# 8T49N241-999NLGI.net
KiCad netlist of a schematic drawn in Altium Designer
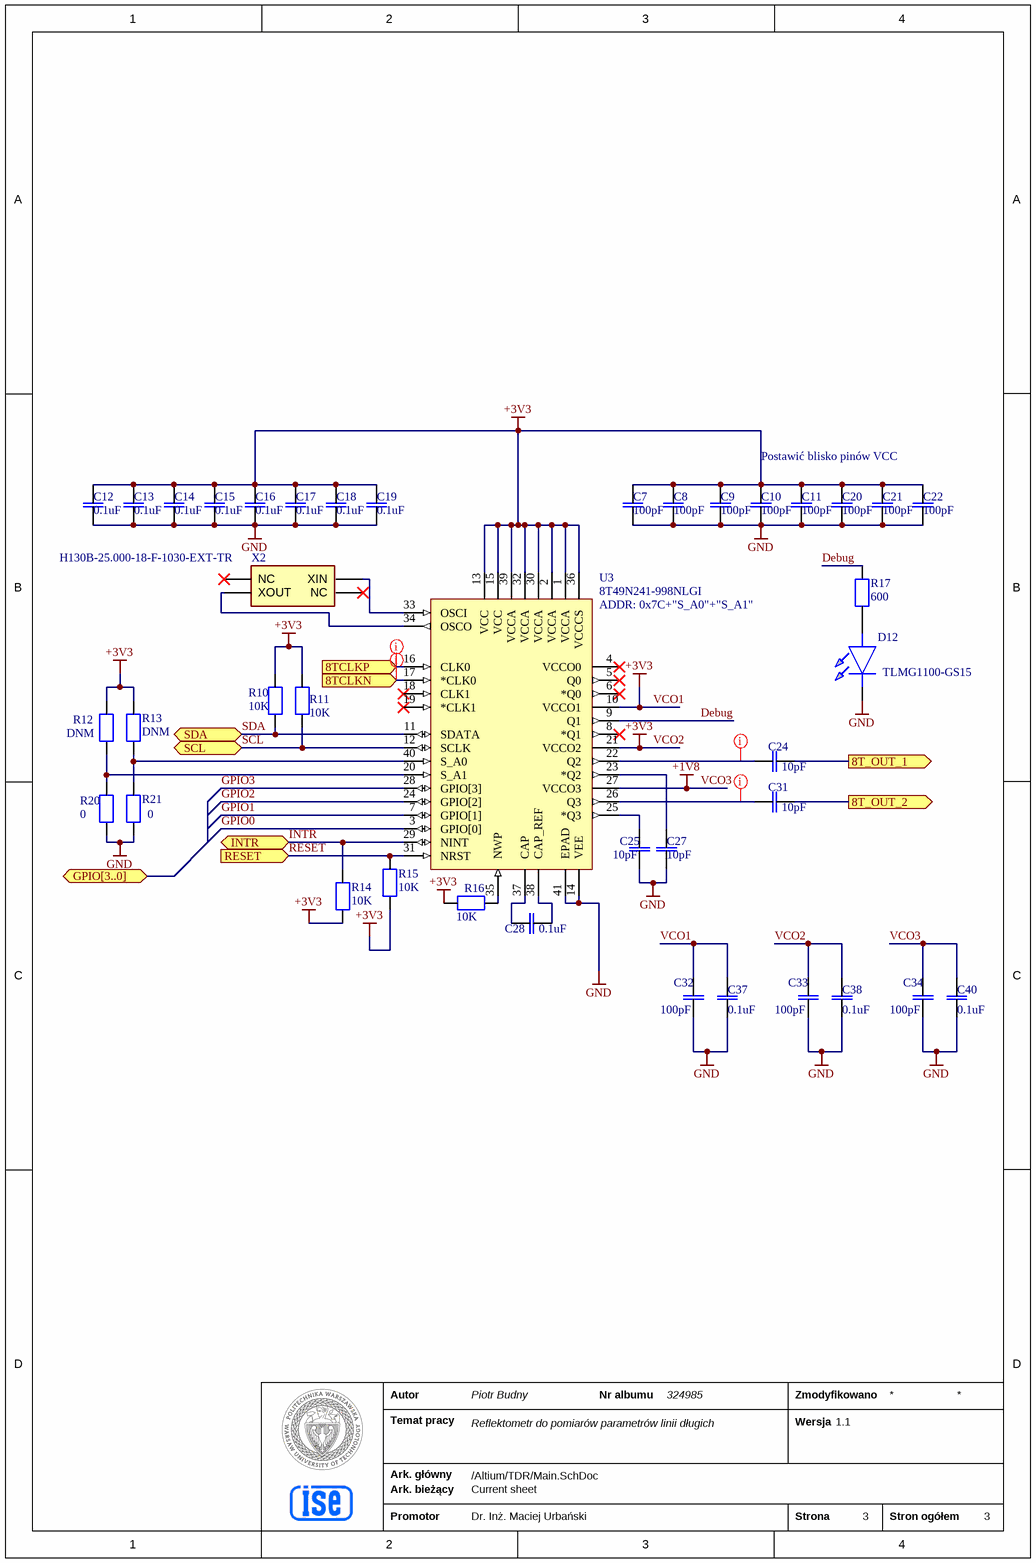
[diagram p0: 8T49N241-999NLGI.SchDoc]

(export (version "E")
  (design (tool "Eeschema 10.0.6"))
  (components
    (comp (ref "C7")
      (value "100pF")
      (footprint "CAPC0603")
      (description "No Description Available")
      (fields
        (field (name "MANUFACTURER_PART_NUMBER") "C0805X399C8HAC7800")
        (field (name "COPYRIGHT") "Copyright (C) 2025 Ultra Librarian. All rights reserved.")
      )
      (libsource (lib "TDR_int_lib") (part "C0603"))
    )
    (comp (ref "C8")
      (value "100pF")
      (footprint "CAPC0603")
      (description "No Description Available")
      (fields
        (field (name "MANUFACTURER_PART_NUMBER") "C0805X399C8HAC7800")
        (field (name "COPYRIGHT") "Copyright (C) 2025 Ultra Librarian. All rights reserved.")
      )
      (libsource (lib "TDR_int_lib") (part "C0603"))
    )
    (comp (ref "C9")
      (value "100pF")
      (footprint "CAPC0603")
      (description "No Description Available")
      (fields
        (field (name "MANUFACTURER_PART_NUMBER") "C0805X399C8HAC7800")
        (field (name "COPYRIGHT") "Copyright (C) 2025 Ultra Librarian. All rights reserved.")
      )
      (libsource (lib "TDR_int_lib") (part "C0603"))
    )
    (comp (ref "C10")
      (value "100pF")
      (footprint "CAPC0603")
      (description "No Description Available")
      (fields
        (field (name "MANUFACTURER_PART_NUMBER") "C0805X399C8HAC7800")
        (field (name "COPYRIGHT") "Copyright (C) 2025 Ultra Librarian. All rights reserved.")
      )
      (libsource (lib "TDR_int_lib") (part "C0603"))
    )
    (comp (ref "C11")
      (value "100pF")
      (footprint "CAPC0603")
      (description "No Description Available")
      (fields
        (field (name "MANUFACTURER_PART_NUMBER") "C0805X399C8HAC7800")
        (field (name "COPYRIGHT") "Copyright (C) 2025 Ultra Librarian. All rights reserved.")
      )
      (libsource (lib "TDR_int_lib") (part "C0603"))
    )
    (comp (ref "C12")
      (value "0.1uF")
      (footprint "CAPC0603")
      (description "CAP SMD 0805")
      (fields
        (field (name "MANUFACTURER_PART_NUMBER") "C0805X399C8HAC7800")
        (field (name "COPYRIGHT") "Copyright (C) 2025 Ultra Librarian. All rights reserved.")
      )
      (libsource (lib "TDR_int_lib") (part "C0603"))
    )
    (comp (ref "C13")
      (value "0.1uF")
      (footprint "CAPC0603")
      (description "CAP SMD 0805")
      (fields
        (field (name "MANUFACTURER_PART_NUMBER") "C0805X399C8HAC7800")
        (field (name "COPYRIGHT") "Copyright (C) 2025 Ultra Librarian. All rights reserved.")
      )
      (libsource (lib "TDR_int_lib") (part "C0603"))
    )
    (comp (ref "C14")
      (value "0.1uF")
      (footprint "CAPC0603")
      (description "CAP SMD 0805")
      (fields
        (field (name "MANUFACTURER_PART_NUMBER") "C0805X399C8HAC7800")
        (field (name "COPYRIGHT") "Copyright (C) 2025 Ultra Librarian. All rights reserved.")
      )
      (libsource (lib "TDR_int_lib") (part "C0603"))
    )
    (comp (ref "C15")
      (value "0.1uF")
      (footprint "CAPC0603")
      (description "CAP SMD 0805")
      (fields
        (field (name "MANUFACTURER_PART_NUMBER") "C0805X399C8HAC7800")
        (field (name "COPYRIGHT") "Copyright (C) 2025 Ultra Librarian. All rights reserved.")
      )
      (libsource (lib "TDR_int_lib") (part "C0603"))
    )
    (comp (ref "C16")
      (value "0.1uF")
      (footprint "CAPC0603")
      (description "CAP SMD 0805")
      (fields
        (field (name "MANUFACTURER_PART_NUMBER") "C0805X399C8HAC7800")
        (field (name "COPYRIGHT") "Copyright (C) 2025 Ultra Librarian. All rights reserved.")
      )
      (libsource (lib "TDR_int_lib") (part "C0603"))
    )
    (comp (ref "C17")
      (value "0.1uF")
      (footprint "CAPC0603")
      (description "CAP SMD 0805")
      (fields
        (field (name "MANUFACTURER_PART_NUMBER") "C0805X399C8HAC7800")
        (field (name "COPYRIGHT") "Copyright (C) 2025 Ultra Librarian. All rights reserved.")
      )
      (libsource (lib "TDR_int_lib") (part "C0603"))
    )
    (comp (ref "C18")
      (value "0.1uF")
      (footprint "CAPC0603")
      (description "CAP SMD 0805")
      (fields
        (field (name "MANUFACTURER_PART_NUMBER") "C0805X399C8HAC7800")
        (field (name "COPYRIGHT") "Copyright (C) 2025 Ultra Librarian. All rights reserved.")
      )
      (libsource (lib "TDR_int_lib") (part "C0603"))
    )
    (comp (ref "C19")
      (value "0.1uF")
      (footprint "CAPC0603")
      (description "CAP SMD 0805")
      (fields
        (field (name "MANUFACTURER_PART_NUMBER") "C0805X399C8HAC7800")
        (field (name "COPYRIGHT") "Copyright (C) 2025 Ultra Librarian. All rights reserved.")
      )
      (libsource (lib "TDR_int_lib") (part "C0603"))
    )
    (comp (ref "C20")
      (value "100pF")
      (footprint "CAPC0603")
      (description "No Description Available")
      (fields
        (field (name "MANUFACTURER_PART_NUMBER") "C0805X399C8HAC7800")
        (field (name "COPYRIGHT") "Copyright (C) 2025 Ultra Librarian. All rights reserved.")
      )
      (libsource (lib "TDR_int_lib") (part "C0603"))
    )
    (comp (ref "C21")
      (value "100pF")
      (footprint "CAPC0603")
      (description "No Description Available")
      (fields
        (field (name "MANUFACTURER_PART_NUMBER") "C0805X399C8HAC7800")
        (field (name "COPYRIGHT") "Copyright (C) 2025 Ultra Librarian. All rights reserved.")
      )
      (libsource (lib "TDR_int_lib") (part "C0603"))
    )
    (comp (ref "C22")
      (value "100pF")
      (footprint "CAPC0603")
      (description "No Description Available")
      (fields
        (field (name "MANUFACTURER_PART_NUMBER") "C0805X399C8HAC7800")
        (field (name "COPYRIGHT") "Copyright (C) 2025 Ultra Librarian. All rights reserved.")
      )
      (libsource (lib "TDR_int_lib") (part "C0603"))
    )
    (comp (ref "C24")
      (value "10pF")
      (footprint "CAPC0402")
      (description "No Description Available")
      (fields
        (field (name "MANUFACTURER_PART_NUMBER") "C0805X399C8HAC7800")
        (field (name "COPYRIGHT") "Copyright (C) 2025 Ultra Librarian. All rights reserved.")
      )
      (libsource (lib "TDR_int_lib") (part "C0603"))
    )
    (comp (ref "C25")
      (value "10pF")
      (footprint "CAPC0402")
      (description "No Description Available")
      (fields
        (field (name "MANUFACTURER_PART_NUMBER") "C0805X399C8HAC7800")
        (field (name "COPYRIGHT") "Copyright (C) 2025 Ultra Librarian. All rights reserved.")
      )
      (libsource (lib "TDR_int_lib") (part "C0603"))
    )
    (comp (ref "C27")
      (value "10pF")
      (footprint "CAPC0402")
      (description "No Description Available")
      (fields
        (field (name "MANUFACTURER_PART_NUMBER") "C0805X399C8HAC7800")
        (field (name "COPYRIGHT") "Copyright (C) 2025 Ultra Librarian. All rights reserved.")
      )
      (libsource (lib "TDR_int_lib") (part "C0603"))
    )
    (comp (ref "C28")
      (value "0.1uF")
      (footprint "CAPC0603")
      (description "CAP SMD 0603")
      (fields
        (field (name "MANUFACTURER_PART_NUMBER") "C0805X399C8HAC7800")
        (field (name "COPYRIGHT") "Copyright (C) 2025 Ultra Librarian. All rights reserved.")
      )
      (libsource (lib "TDR_int_lib") (part "C0603"))
    )
    (comp (ref "C31")
      (value "10pF")
      (footprint "CAPC0402")
      (description "No Description Available")
      (fields
        (field (name "MANUFACTURER_PART_NUMBER") "C0805X399C8HAC7800")
        (field (name "COPYRIGHT") "Copyright (C) 2025 Ultra Librarian. All rights reserved.")
      )
      (libsource (lib "TDR_int_lib") (part "C0603"))
    )
    (comp (ref "C32")
      (value "100pF")
      (footprint "CAPC0603")
      (description "No Description Available")
      (fields
        (field (name "MANUFACTURER_PART_NUMBER") "C0805X399C8HAC7800")
        (field (name "COPYRIGHT") "Copyright (C) 2025 Ultra Librarian. All rights reserved.")
      )
      (libsource (lib "TDR_int_lib") (part "C0603"))
    )
    (comp (ref "C33")
      (value "100pF")
      (footprint "CAPC0603")
      (description "No Description Available")
      (fields
        (field (name "MANUFACTURER_PART_NUMBER") "C0805X399C8HAC7800")
        (field (name "COPYRIGHT") "Copyright (C) 2025 Ultra Librarian. All rights reserved.")
      )
      (libsource (lib "TDR_int_lib") (part "C0603"))
    )
    (comp (ref "C34")
      (value "100pF")
      (footprint "CAPC0603")
      (description "No Description Available")
      (fields
        (field (name "MANUFACTURER_PART_NUMBER") "C0805X399C8HAC7800")
        (field (name "COPYRIGHT") "Copyright (C) 2025 Ultra Librarian. All rights reserved.")
      )
      (libsource (lib "TDR_int_lib") (part "C0603"))
    )
    (comp (ref "C37")
      (value "0.1uF")
      (footprint "CAPC0603")
      (description "CAP SMD 0805")
      (fields
        (field (name "MANUFACTURER_PART_NUMBER") "C0805X399C8HAC7800")
        (field (name "COPYRIGHT") "Copyright (C) 2025 Ultra Librarian. All rights reserved.")
      )
      (libsource (lib "TDR_int_lib") (part "C0603"))
    )
    (comp (ref "C38")
      (value "0.1uF")
      (footprint "CAPC0603")
      (description "CAP SMD 0805")
      (fields
        (field (name "MANUFACTURER_PART_NUMBER") "C0805X399C8HAC7800")
        (field (name "COPYRIGHT") "Copyright (C) 2025 Ultra Librarian. All rights reserved.")
      )
      (libsource (lib "TDR_int_lib") (part "C0603"))
    )
    (comp (ref "C40")
      (value "0.1uF")
      (footprint "CAPC0603")
      (description "CAP SMD 0805")
      (fields
        (field (name "MANUFACTURER_PART_NUMBER") "C0805X399C8HAC7800")
        (field (name "COPYRIGHT") "Copyright (C) 2025 Ultra Librarian. All rights reserved.")
      )
      (libsource (lib "TDR_int_lib") (part "C0603"))
    )
    (comp (ref "D12")
      (value "TLMG1100-GS15")
      (footprint "TLMG1100GS15")
      (description "Standard LEDs - SMD CHIPLED(SMD 0603-LED) GREEN U.BRIGHT-E4")
      (fields (field (name "MOUSER PART NUMBER") "78-TLMG1100-GS15"))
      (libsource (lib "TDR_int_lib") (part "TLMG1100-GS15"))
    )
    (comp (ref "R10")
      (value "10K")
      (footprint "RES0805")
      (description "RES SMD 0805")
      (fields (field (name "MP") "RT0805FRE075K36L"))
      (libsource (lib "TDR_int_lib") (part "R0805"))
    )
    (comp (ref "R11")
      (value "10K")
      (footprint "RES0805")
      (description "RES SMD 0805")
      (fields (field (name "MP") "RT0805FRE075K36L"))
      (libsource (lib "TDR_int_lib") (part "R0805"))
    )
    (comp (ref "R12")
      (value "DNM")
      (footprint "RES0805")
      (description "RES SMD 0805")
      (fields (field (name "MP") "RT0805FRE075K36L"))
      (libsource (lib "TDR_int_lib") (part "R0805"))
    )
    (comp (ref "R13")
      (value "DNM")
      (footprint "RES0805")
      (description "RES SMD 0805")
      (fields (field (name "MP") "RT0805FRE075K36L"))
      (libsource (lib "TDR_int_lib") (part "R0805"))
    )
    (comp (ref "R14")
      (value "10K")
      (footprint "RES0805")
      (description "RES SMD 0805")
      (fields (field (name "MP") "RT0805FRE075K36L"))
      (libsource (lib "TDR_int_lib") (part "R0805"))
    )
    (comp (ref "R15")
      (value "10K")
      (footprint "RES0805")
      (description "RES SMD 0805")
      (fields (field (name "MP") "RT0805FRE075K36L"))
      (libsource (lib "TDR_int_lib") (part "R0805"))
    )
    (comp (ref "R16")
      (value "10K")
      (footprint "RES0805")
      (description "RES SMD 0805")
      (fields (field (name "MP") "RT0805FRE075K36L"))
      (libsource (lib "TDR_int_lib") (part "R0805"))
    )
    (comp (ref "R17")
      (value "600")
      (footprint "RES0805")
      (description "RES SMD 0805")
      (fields (field (name "MP") "RT0805FRE075K36L"))
      (libsource (lib "TDR_int_lib") (part "R0805"))
    )
    (comp (ref "R20")
      (value "0")
      (footprint "RES0805")
      (description "RES SMD 0805")
      (fields (field (name "MP") "RT0805FRE075K36L"))
      (libsource (lib "TDR_int_lib") (part "R0805"))
    )
    (comp (ref "R21")
      (value "0")
      (footprint "RES0805")
      (description "RES SMD 0805")
      (fields (field (name "MP") "RT0805FRE075K36L"))
      (libsource (lib "TDR_int_lib") (part "R0805"))
    )
    (comp (ref "U3")
      (value "8T49N241-998NLGI")
      (footprint "NLG40P2_MFG")
      (description "Tin Active e3 CLOCK GENERATOR OTHER (Type) IC 18Weeks -40C 6mm 1GHz")
      (libsource (lib "TDR_int_lib") (part "8T49N241-999NLGI"))
    )
    (comp (ref "X2")
      (value "H130B-25.000-18-F-1030-EXT-TR")
      (footprint "H130B2500018F1030EXTTR")
      (description "MHz Crystal, 25 MHz, 5 x 3.2 mm, +/-10 ppm tolerance, +/-30 ppm stability, 18 pF, -40~85C, SMD")
      (libsource (lib "TDR_int_lib") (part "H130B-25.000-18-F-1030-EXT-TR"))
    )
  )
  (nets
    (net (code "1") (name "+1V8") (class "Default")
      (node (ref "C34") (pin "1") (pinfunction "1_1") (pintype "passive"))
      (node (ref "C40") (pin "2") (pinfunction "2_2") (pintype "passive"))
      (node (ref "U3") (pin "27") (pinfunction "VCCO3_27") (pintype "power_in"))
    )
    (net (code "2") (name "+3V3") (class "Default")
      (node (ref "C10") (pin "1") (pinfunction "1_1") (pintype "passive"))
      (node (ref "C11") (pin "1") (pinfunction "1_1") (pintype "passive"))
      (node (ref "C12") (pin "2") (pinfunction "2_2") (pintype "passive"))
      (node (ref "C13") (pin "2") (pinfunction "2_2") (pintype "passive"))
      (node (ref "C14") (pin "2") (pinfunction "2_2") (pintype "passive"))
      (node (ref "C15") (pin "2") (pinfunction "2_2") (pintype "passive"))
      (node (ref "C16") (pin "2") (pinfunction "2_2") (pintype "passive"))
      (node (ref "C17") (pin "2") (pinfunction "2_2") (pintype "passive"))
      (node (ref "C18") (pin "2") (pinfunction "2_2") (pintype "passive"))
      (node (ref "C19") (pin "2") (pinfunction "2_2") (pintype "passive"))
      (node (ref "C20") (pin "1") (pinfunction "1_1") (pintype "passive"))
      (node (ref "C21") (pin "1") (pinfunction "1_1") (pintype "passive"))
      (node (ref "C22") (pin "1") (pinfunction "1_1") (pintype "passive"))
      (node (ref "C32") (pin "1") (pinfunction "1_1") (pintype "passive"))
      (node (ref "C33") (pin "1") (pinfunction "1_1") (pintype "passive"))
      (node (ref "C37") (pin "2") (pinfunction "2_2") (pintype "passive"))
      (node (ref "C38") (pin "2") (pinfunction "2_2") (pintype "passive"))
      (node (ref "C7") (pin "1") (pinfunction "1_1") (pintype "passive"))
      (node (ref "C8") (pin "1") (pinfunction "1_1") (pintype "passive"))
      (node (ref "C9") (pin "1") (pinfunction "1_1") (pintype "passive"))
      (node (ref "R10") (pin "2") (pinfunction "2_2") (pintype "passive"))
      (node (ref "R11") (pin "2") (pinfunction "2_2") (pintype "passive"))
      (node (ref "R12") (pin "2") (pinfunction "2_2") (pintype "passive"))
      (node (ref "R13") (pin "2") (pinfunction "2_2") (pintype "passive"))
      (node (ref "R14") (pin "1") (pinfunction "1_1") (pintype "passive"))
      (node (ref "R15") (pin "1") (pinfunction "1_1") (pintype "passive"))
      (node (ref "R16") (pin "2") (pinfunction "2_2") (pintype "passive"))
      (node (ref "U3") (pin "1") (pinfunction "VCCA_1") (pintype "power_in"))
      (node (ref "U3") (pin "10") (pinfunction "VCCO1_10") (pintype "power_in"))
      (node (ref "U3") (pin "13") (pinfunction "VCC_13") (pintype "power_in"))
      (node (ref "U3") (pin "15") (pinfunction "VCC_15") (pintype "power_in"))
      (node (ref "U3") (pin "2") (pinfunction "VCCA_2") (pintype "power_in"))
      (node (ref "U3") (pin "21") (pinfunction "VCCO2_21") (pintype "power_in"))
      (node (ref "U3") (pin "30") (pinfunction "VCCA_30") (pintype "power_in"))
      (node (ref "U3") (pin "32") (pinfunction "VCCA_32") (pintype "power_in"))
      (node (ref "U3") (pin "36") (pinfunction "VCCCS_36") (pintype "power_in"))
      (node (ref "U3") (pin "39") (pinfunction "VCCA_39") (pintype "power_in"))
    )
    (net (code "3") (name "/8TCLKN") (class "Default")
      (node (ref "U3") (pin "17") (pinfunction "*CLK0_17") (pintype "input"))
    )
    (net (code "4") (name "/8TCLKP") (class "Default")
      (node (ref "U3") (pin "16") (pinfunction "CLK0_16") (pintype "input"))
    )
    (net (code "5") (name "/8T_OUT_1") (class "Default")
      (node (ref "C24") (pin "2") (pinfunction "2_2") (pintype "passive"))
    )
    (net (code "6") (name "/8T_OUT_2") (class "Default")
      (node (ref "C31") (pin "2") (pinfunction "2_2") (pintype "passive"))
    )
    (net (code "7") (name "/Debug") (class "Default")
      (node (ref "R17") (pin "1") (pinfunction "1_1") (pintype "passive"))
      (node (ref "U3") (pin "9") (pinfunction "Q1_9") (pintype "output"))
    )
    (net (code "8") (name "/GPIO0") (class "Default")
      (node (ref "U3") (pin "3") (pinfunction "GPIO[0]_3") (pintype "bidirectional"))
    )
    (net (code "9") (name "/GPIO1") (class "Default")
      (node (ref "U3") (pin "7") (pinfunction "GPIO[1]_7") (pintype "bidirectional"))
    )
    (net (code "10") (name "/GPIO2") (class "Default")
      (node (ref "U3") (pin "24") (pinfunction "GPIO[2]_24") (pintype "bidirectional"))
    )
    (net (code "11") (name "/GPIO3") (class "Default")
      (node (ref "U3") (pin "28") (pinfunction "GPIO[3]_28") (pintype "bidirectional"))
    )
    (net (code "13") (name "/INTR") (class "Default")
      (node (ref "R14") (pin "2") (pinfunction "2_2") (pintype "passive"))
      (node (ref "U3") (pin "29") (pinfunction "NINT_29") (pintype "bidirectional"))
    )
    (net (code "14") (name "/RESET") (class "Default")
      (node (ref "R15") (pin "2") (pinfunction "2_2") (pintype "passive"))
      (node (ref "U3") (pin "31") (pinfunction "NRST_31") (pintype "input"))
    )
    (net (code "15") (name "/SCL") (class "Default")
      (node (ref "R11") (pin "1") (pinfunction "1_1") (pintype "passive"))
      (node (ref "U3") (pin "12") (pinfunction "SCLK_12") (pintype "bidirectional"))
    )
    (net (code "16") (name "/SDA") (class "Default")
      (node (ref "R10") (pin "1") (pinfunction "1_1") (pintype "passive"))
      (node (ref "U3") (pin "11") (pinfunction "SDATA_11") (pintype "bidirectional"))
    )
    (net (code "17") (name "GND") (class "Default")
      (node (ref "C10") (pin "2") (pinfunction "2_2") (pintype "passive"))
      (node (ref "C11") (pin "2") (pinfunction "2_2") (pintype "passive"))
      (node (ref "C12") (pin "1") (pinfunction "1_1") (pintype "passive"))
      (node (ref "C13") (pin "1") (pinfunction "1_1") (pintype "passive"))
      (node (ref "C14") (pin "1") (pinfunction "1_1") (pintype "passive"))
      (node (ref "C15") (pin "1") (pinfunction "1_1") (pintype "passive"))
      (node (ref "C16") (pin "1") (pinfunction "1_1") (pintype "passive"))
      (node (ref "C17") (pin "1") (pinfunction "1_1") (pintype "passive"))
      (node (ref "C18") (pin "1") (pinfunction "1_1") (pintype "passive"))
      (node (ref "C19") (pin "1") (pinfunction "1_1") (pintype "passive"))
      (node (ref "C20") (pin "2") (pinfunction "2_2") (pintype "passive"))
      (node (ref "C21") (pin "2") (pinfunction "2_2") (pintype "passive"))
      (node (ref "C22") (pin "2") (pinfunction "2_2") (pintype "passive"))
      (node (ref "C25") (pin "1") (pinfunction "1_1") (pintype "passive"))
      (node (ref "C27") (pin "1") (pinfunction "1_1") (pintype "passive"))
      (node (ref "C32") (pin "2") (pinfunction "2_2") (pintype "passive"))
      (node (ref "C33") (pin "2") (pinfunction "2_2") (pintype "passive"))
      (node (ref "C34") (pin "2") (pinfunction "2_2") (pintype "passive"))
      (node (ref "C37") (pin "1") (pinfunction "1_1") (pintype "passive"))
      (node (ref "C38") (pin "1") (pinfunction "1_1") (pintype "passive"))
      (node (ref "C40") (pin "1") (pinfunction "1_1") (pintype "passive"))
      (node (ref "C7") (pin "2") (pinfunction "2_2") (pintype "passive"))
      (node (ref "C8") (pin "2") (pinfunction "2_2") (pintype "passive"))
      (node (ref "C9") (pin "2") (pinfunction "2_2") (pintype "passive"))
      (node (ref "D12") (pin "1") (pinfunction "K_1") (pintype "passive"))
      (node (ref "R20") (pin "1") (pinfunction "1_1") (pintype "passive"))
      (node (ref "R21") (pin "1") (pinfunction "1_1") (pintype "passive"))
      (node (ref "U3") (pin "14") (pinfunction "VEE_14") (pintype "power_in"))
      (node (ref "U3") (pin "41") (pinfunction "EPAD_41") (pintype "power_in"))
    )
    (net (code "18") (name "Net-(D12-A)") (class "Default")
      (node (ref "D12") (pin "2") (pinfunction "A_2") (pintype "passive"))
      (node (ref "R17") (pin "2") (pinfunction "2_2") (pintype "passive"))
    )
    (net (code "19") (name "Net-(U3-*Q2)") (class "Default")
      (node (ref "C27") (pin "2") (pinfunction "2_2") (pintype "passive"))
      (node (ref "U3") (pin "23") (pinfunction "*Q2_23") (pintype "output"))
    )
    (net (code "20") (name "Net-(U3-*Q3)") (class "Default")
      (node (ref "C25") (pin "2") (pinfunction "2_2") (pintype "passive"))
      (node (ref "U3") (pin "25") (pinfunction "*Q3_25") (pintype "output"))
    )
    (net (code "21") (name "Net-(U3-CAP)") (class "Default")
      (node (ref "C28") (pin "2") (pinfunction "2_2") (pintype "passive"))
      (node (ref "U3") (pin "37") (pinfunction "CAP_37") (pintype "passive"))
    )
    (net (code "22") (name "Net-(U3-CAP_REF)") (class "Default")
      (node (ref "C28") (pin "1") (pinfunction "1_1") (pintype "passive"))
      (node (ref "U3") (pin "38") (pinfunction "CAP_REF_38") (pintype "passive"))
    )
    (net (code "23") (name "Net-(U3-NWP)") (class "Default")
      (node (ref "R16") (pin "1") (pinfunction "1_1") (pintype "passive"))
      (node (ref "U3") (pin "35") (pinfunction "NWP_35") (pintype "input"))
    )
    (net (code "24") (name "Net-(U3-OSCI)") (class "Default")
      (node (ref "U3") (pin "33") (pinfunction "OSCI_33") (pintype "input"))
      (node (ref "X2") (pin "1") (pinfunction "XIN_1") (pintype "passive"))
    )
    (net (code "25") (name "Net-(U3-OSCO)") (class "Default")
      (node (ref "U3") (pin "34") (pinfunction "OSCO_34") (pintype "output"))
      (node (ref "X2") (pin "3") (pinfunction "XOUT_3") (pintype "passive"))
    )
    (net (code "26") (name "Net-(U3-Q2)") (class "Default")
      (node (ref "C24") (pin "1") (pinfunction "1_1") (pintype "passive"))
      (node (ref "U3") (pin "22") (pinfunction "Q2_22") (pintype "output"))
    )
    (net (code "27") (name "Net-(U3-Q3)") (class "Default")
      (node (ref "C31") (pin "1") (pinfunction "1_1") (pintype "passive"))
      (node (ref "U3") (pin "26") (pinfunction "Q3_26") (pintype "output"))
    )
    (net (code "28") (name "Net-(U3-S_A0)") (class "Default")
      (node (ref "R13") (pin "1") (pinfunction "1_1") (pintype "passive"))
      (node (ref "R21") (pin "2") (pinfunction "2_2") (pintype "passive"))
      (node (ref "U3") (pin "40") (pinfunction "S_A0_40") (pintype "input"))
    )
    (net (code "29") (name "Net-(U3-S_A1)") (class "Default")
      (node (ref "R12") (pin "1") (pinfunction "1_1") (pintype "passive"))
      (node (ref "R20") (pin "2") (pinfunction "2_2") (pintype "passive"))
      (node (ref "U3") (pin "20") (pinfunction "S_A1_20") (pintype "input"))
    )
    (net (code "30") (name "unconnected-(U3-*CLK1-Pad19)") (class "Default")
      (node (ref "U3") (pin "19") (pinfunction "*CLK1_19") (pintype "input+no_connect"))
    )
    (net (code "31") (name "unconnected-(U3-*Q0-Pad6)") (class "Default")
      (node (ref "U3") (pin "6") (pinfunction "*Q0_6") (pintype "output+no_connect"))
    )
    (net (code "32") (name "unconnected-(U3-*Q1-Pad8)") (class "Default")
      (node (ref "U3") (pin "8") (pinfunction "*Q1_8") (pintype "output+no_connect"))
    )
    (net (code "33") (name "unconnected-(U3-CLK1-Pad18)") (class "Default")
      (node (ref "U3") (pin "18") (pinfunction "CLK1_18") (pintype "input+no_connect"))
    )
    (net (code "34") (name "unconnected-(U3-Q0-Pad5)") (class "Default")
      (node (ref "U3") (pin "5") (pinfunction "Q0_5") (pintype "output+no_connect"))
    )
    (net (code "35") (name "unconnected-(U3-VCCO0-Pad4)") (class "Default")
      (node (ref "U3") (pin "4") (pinfunction "VCCO0_4") (pintype "power_in+no_connect"))
    )
    (net (code "36") (name "unconnected-(X2-NC-Pad2)") (class "Default")
      (node (ref "X2") (pin "2") (pinfunction "NC_2") (pintype "passive+no_connect"))
    )
    (net (code "37") (name "unconnected-(X2-NC-Pad4)") (class "Default")
      (node (ref "X2") (pin "4") (pinfunction "NC_4") (pintype "passive+no_connect"))
    )
  )
)
